# STM32L441CE_4L-connector_1mm_pitch.net
KiCad netlist of a schematic drawn in EAGLE
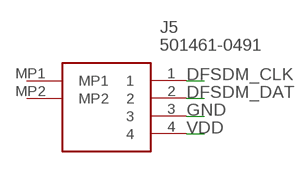
[diagram p0: schematic, sheet 1]
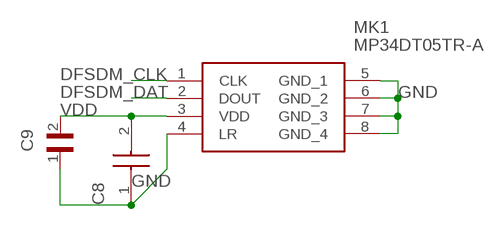
[diagram p1: schematic, sheet 2]

(export (version "E")
  (design (tool "Eeschema 10.0.6"))
  (components
    (comp (ref "C8")
      (value "AMK063AC6105KP-F")
      (footprint "eagle-import:CAPC0603X33N")
      (fields (field (name "MOUSER_PART_NUMBER") "963-AMK063AC6105KP-F"))
      (libsource (lib "eagle-import") (part "AMK063AC6105KP-F"))
    )
    (comp (ref "C9")
      (value "GRM033C80J104KE15D")
      (footprint "eagle-import:CAPC0603X33N")
      (fields (field (name "DIGI-KEY_PART_NUMBER") "490-10390-1-ND") (field (name "MF") "Murata Electronics"))
      (libsource (lib "eagle-import") (part "GRM033C80J104KE15D"))
    )
    (comp (ref "MK1")
      (value "MP34DT05TR-A")
      (footprint "eagle-import:MP34DT05TRA")
      (fields (field (name "MOUSER_PART_NUMBER") "511-MP34DT05TR-A"))
      (libsource (lib "eagle-import") (part "MP34DT05TR-A"))
    )
    (comp (ref "J5")
      (value "501461-0491")
      (footprint "eagle-import:5014610491")
      (fields (field (name "MOUSER_PART_NUMBER") "538-501461-0491"))
      (libsource (lib "eagle-import") (part "501461-0491"))
    )
  )
  (nets
    (net (code "1") (name "DFSDM_CLK") (class "Default")
      (node (ref "J5") (pin "1") (pinfunction "1_1") (pintype "bidirectional"))
      (node (ref "MK1") (pin "1") (pinfunction "CLK_1") (pintype "bidirectional"))
    )
    (net (code "2") (name "DFSDM_DAT") (class "Default")
      (node (ref "J5") (pin "2") (pinfunction "2_2") (pintype "bidirectional"))
      (node (ref "MK1") (pin "2") (pinfunction "DOUT_2") (pintype "bidirectional"))
    )
    (net (code "3") (name "GND") (class "Default")
      (node (ref "C8") (pin "1") (pinfunction "1_1") (pintype "bidirectional"))
      (node (ref "C9") (pin "1") (pinfunction "1_1") (pintype "passive"))
      (node (ref "J5") (pin "3") (pinfunction "3_3") (pintype "bidirectional"))
      (node (ref "MK1") (pin "4") (pinfunction "LR_4") (pintype "bidirectional"))
      (node (ref "MK1") (pin "5") (pinfunction "GND_1_5") (pintype "bidirectional"))
      (node (ref "MK1") (pin "6") (pinfunction "GND_2_6") (pintype "bidirectional"))
      (node (ref "MK1") (pin "7") (pinfunction "GND_3_7") (pintype "bidirectional"))
      (node (ref "MK1") (pin "8") (pinfunction "GND_4_8") (pintype "bidirectional"))
    )
    (net (code "4") (name "VDD") (class "Default")
      (node (ref "C8") (pin "2") (pinfunction "2_2") (pintype "bidirectional"))
      (node (ref "C9") (pin "2") (pinfunction "2_2") (pintype "passive"))
      (node (ref "J5") (pin "4") (pinfunction "4_4") (pintype "bidirectional"))
      (node (ref "MK1") (pin "3") (pinfunction "VDD_3") (pintype "bidirectional"))
    )
    (net (code "5") (name "unconnected-(J5-PadMP1)") (class "Default")
      (node (ref "J5") (pin "MP1") (pinfunction "MP1_MP1") (pintype "bidirectional"))
    )
    (net (code "6") (name "unconnected-(J5-PadMP2)") (class "Default")
      (node (ref "J5") (pin "MP2") (pinfunction "MP2_MP2") (pintype "bidirectional"))
    )
  )
)
